# ESP8266_schematic.net
KiCad netlist of a schematic drawn in EAGLE
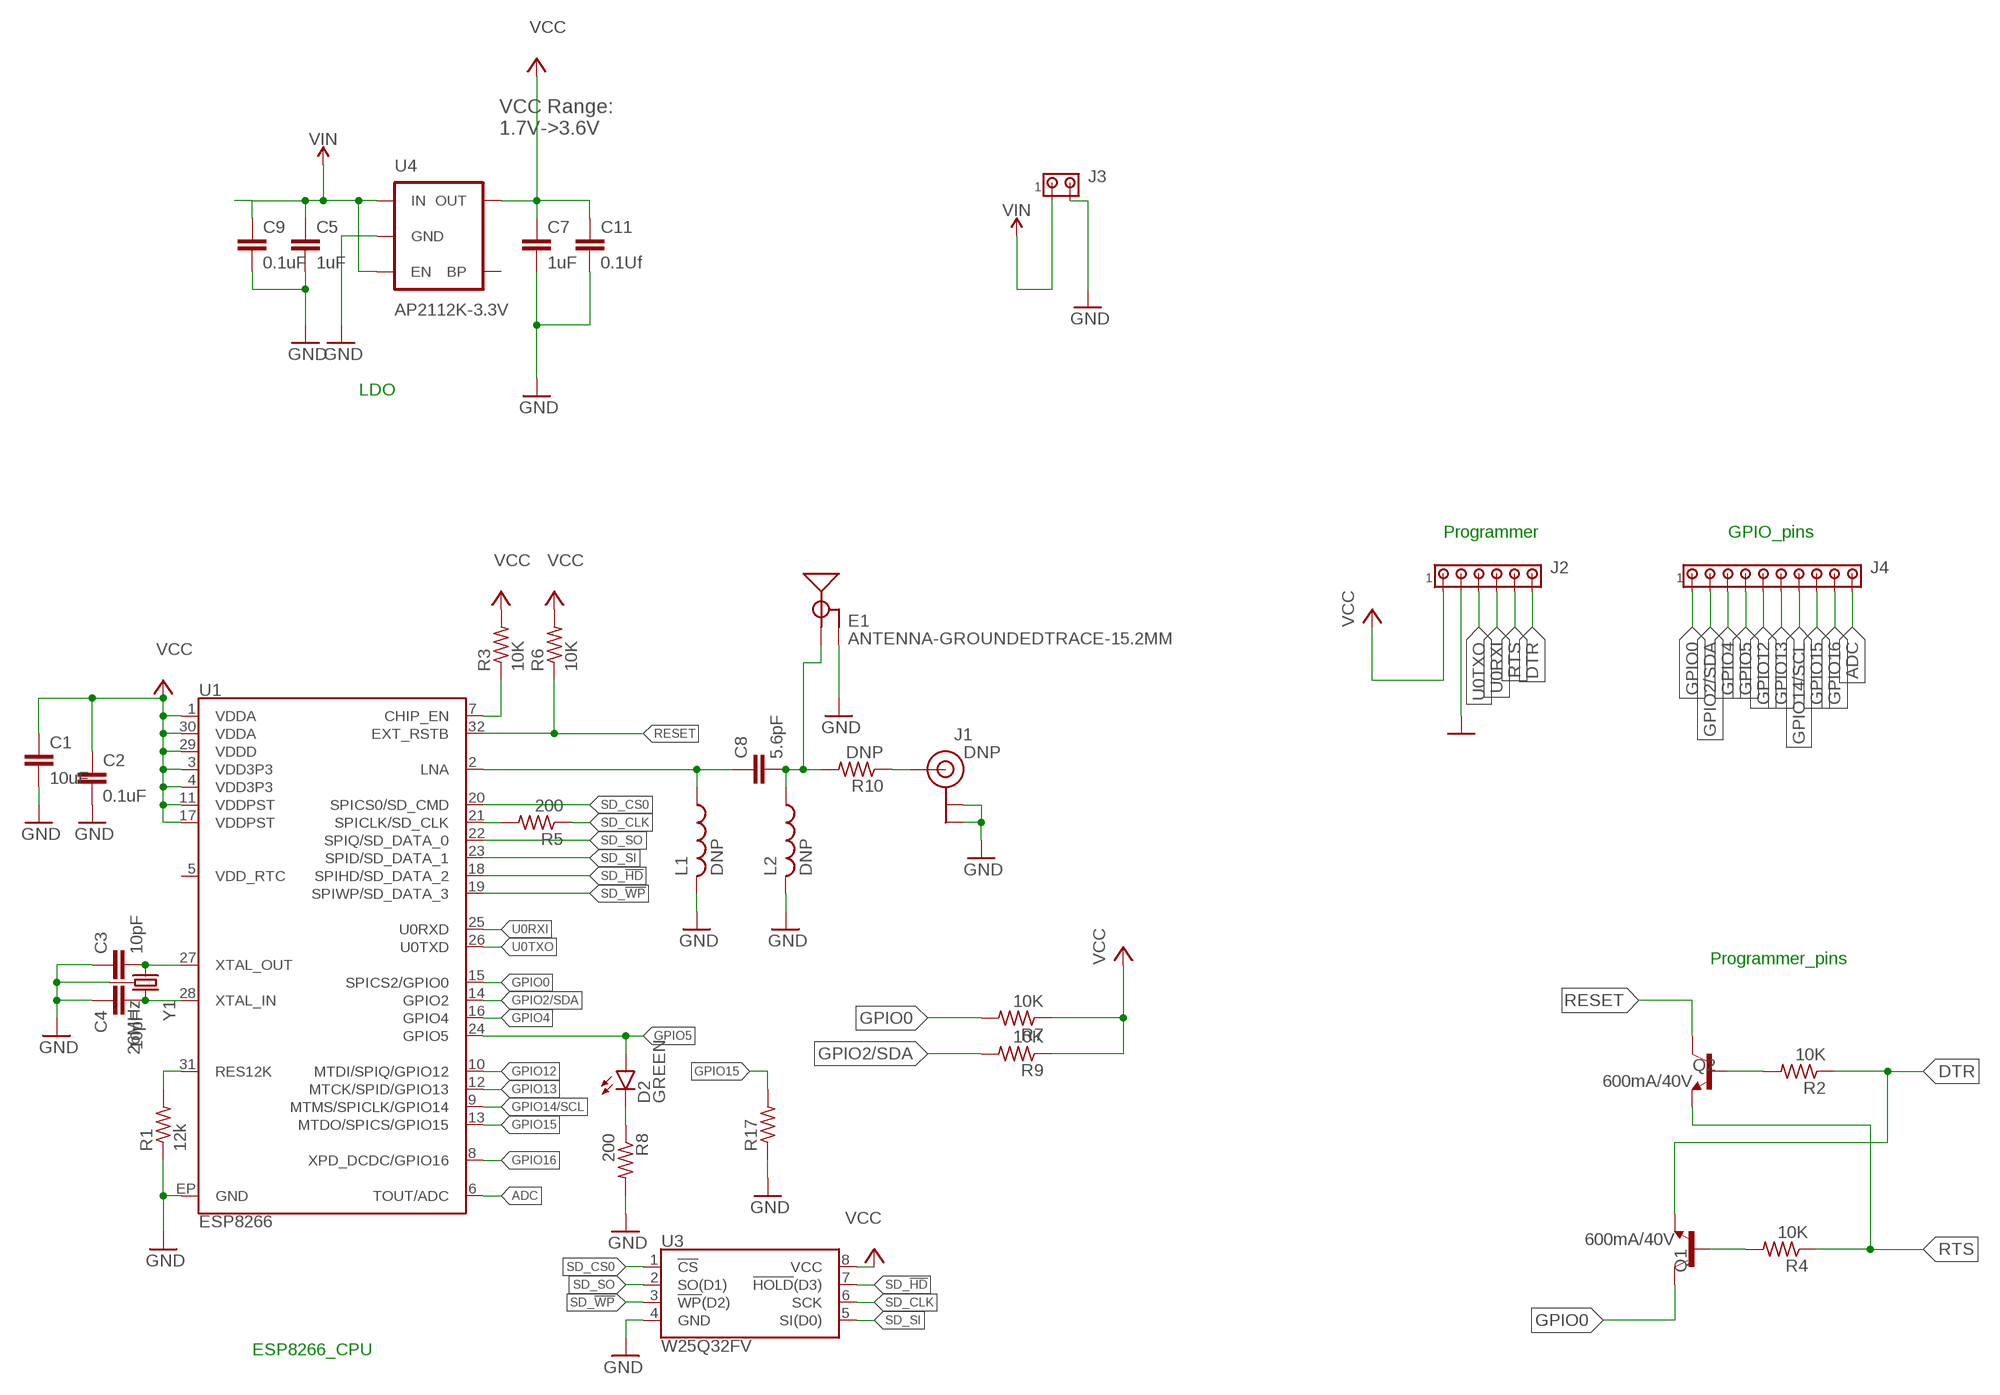
[diagram p0: schematic, sheet 1]

(export (version "E")
  (design (tool "Eeschema 10.0.6"))
  (components
    (comp (ref "C1")
      (value "10uF")
      (footprint "eagle-import:C0603")
      (libsource (lib "eagle-import") (part "resistor_C-EUC0603"))
    )
    (comp (ref "C2")
      (value "0.1uF")
      (footprint "eagle-import:C0603")
      (libsource (lib "eagle-import") (part "resistor_C-EUC0603"))
    )
    (comp (ref "C3")
      (value "10pF")
      (footprint "eagle-import:C0603")
      (libsource (lib "eagle-import") (part "C-EUC0603"))
    )
    (comp (ref "C4")
      (value "10pF")
      (footprint "eagle-import:C0603")
      (libsource (lib "eagle-import") (part "C-EUC0603"))
    )
    (comp (ref "C5")
      (value "1uF")
      (footprint "eagle-import:C0603")
      (libsource (lib "eagle-import") (part "C-EUC0603"))
    )
    (comp (ref "C7")
      (value "1uF")
      (footprint "eagle-import:C0603")
      (libsource (lib "eagle-import") (part "C-EUC0603"))
    )
    (comp (ref "C8")
      (value "5.6pF")
      (footprint "eagle-import:C0603")
      (libsource (lib "eagle-import") (part "C-EUC0603"))
    )
    (comp (ref "C9")
      (value "0.1uF")
      (footprint "eagle-import:C0603")
      (libsource (lib "eagle-import") (part "C-EUC0603"))
    )
    (comp (ref "C11")
      (value "0.1Uf")
      (footprint "eagle-import:C0603")
      (libsource (lib "eagle-import") (part "C-EUC0603"))
    )
    (comp (ref "D2")
      (value "GREEN")
      (footprint "eagle-import:LED-0603")
      (libsource (lib "eagle-import") (part "LED-GREEN0603"))
    )
    (comp (ref "E1")
      (value "ANTENNA-GROUNDEDTRACE-15.2MM")
      (footprint "eagle-import:TRACE_ANTENNA_2.4GHZ_15.2MM")
      (libsource (lib "eagle-import") (part "ANTENNA-GROUNDEDTRACE-15.2MM"))
    )
    (comp (ref "J1")
      (value "DNP")
      (footprint "eagle-import:U.FL")
      (libsource (lib "eagle-import") (part "U.FL"))
    )
    (comp (ref "J2")
      (value "MTA06-100")
      (footprint "eagle-import:10X06MTA")
      (libsource (lib "eagle-import") (part "MTA06-100"))
    )
    (comp (ref "J3")
      (value "MTA02-100")
      (footprint "eagle-import:10X02MTA")
      (libsource (lib "eagle-import") (part "MTA02-100"))
    )
    (comp (ref "J4")
      (value "MTA10-100")
      (footprint "eagle-import:10X10MTA")
      (libsource (lib "eagle-import") (part "MTA10-100"))
    )
    (comp (ref "L1")
      (value "DNP")
      (footprint "eagle-import:L0603")
      (libsource (lib "eagle-import") (part "L-USL0603"))
    )
    (comp (ref "L2")
      (value "DNP")
      (footprint "eagle-import:L0603")
      (libsource (lib "eagle-import") (part "L-USL0603"))
    )
    (comp (ref "Q1")
      (value "600mA/40V")
      (footprint "eagle-import:SOT23-3")
      (libsource (lib "eagle-import") (part "TRANS_NPN-MMBT2222AL"))
    )
    (comp (ref "Q2")
      (value "600mA/40V")
      (footprint "eagle-import:SOT23-3")
      (libsource (lib "eagle-import") (part "TRANS_NPN-MMBT2222AL"))
    )
    (comp (ref "R1")
      (value "12k")
      (footprint "eagle-import:R0805")
      (libsource (lib "eagle-import") (part "R-US_R0805"))
    )
    (comp (ref "R2")
      (value "10K")
      (footprint "eagle-import:R0805")
      (libsource (lib "eagle-import") (part "R-US_R0805"))
    )
    (comp (ref "R3")
      (value "10K")
      (footprint "eagle-import:R0805")
      (libsource (lib "eagle-import") (part "R-US_R0805"))
    )
    (comp (ref "R4")
      (value "10K")
      (footprint "eagle-import:R0805")
      (libsource (lib "eagle-import") (part "R-US_R0805"))
    )
    (comp (ref "R5")
      (value "200")
      (footprint "eagle-import:R0805")
      (libsource (lib "eagle-import") (part "R-US_R0805"))
    )
    (comp (ref "R6")
      (value "10K")
      (footprint "eagle-import:R0805")
      (libsource (lib "eagle-import") (part "R-US_R0805"))
    )
    (comp (ref "R7")
      (value "10K")
      (footprint "eagle-import:R0805")
      (libsource (lib "eagle-import") (part "R-US_R0805"))
    )
    (comp (ref "R8")
      (value "200")
      (footprint "eagle-import:R0805")
      (libsource (lib "eagle-import") (part "R-US_R0805"))
    )
    (comp (ref "R9")
      (value "10K")
      (footprint "eagle-import:R0805")
      (libsource (lib "eagle-import") (part "R-US_R0805"))
    )
    (comp (ref "R10")
      (value "DNP")
      (footprint "eagle-import:R0805")
      (libsource (lib "eagle-import") (part "R-US_R0805"))
    )
    (comp (ref "R17")
      (value "10K")
      (footprint "eagle-import:R0805")
      (libsource (lib "eagle-import") (part "R-US_R0805"))
    )
    (comp (ref "U1")
      (value "ESP8266")
      (footprint "eagle-import:QFN32")
      (libsource (lib "eagle-import") (part "ESP8266"))
    )
    (comp (ref "U3")
      (value "W25Q32FV")
      (footprint "eagle-import:SOIC-8")
      (libsource (lib "eagle-import") (part "W25Q32FVSS"))
    )
    (comp (ref "U4")
      (value "AP2112K-3.3V")
      (footprint "eagle-import:SOT23-5")
      (libsource (lib "eagle-import") (part "V_REG_LDOSMD"))
    )
    (comp (ref "Y1")
      (value "26MHz")
      (footprint "eagle-import:CRYSTAL-SMD-3.2X2.5")
      (libsource (lib "eagle-import") (part "CRYSTAL-GROUNDED3.2X2.5"))
    )
  )
  (nets
    (net (code "1") (name "/SD_~{HD}") (class "Default")
      (node (ref "U1") (pin "18") (pinfunction "SPIHD/SD_DATA_2_18") (pintype "bidirectional"))
      (node (ref "U3") (pin "7") (pinfunction "~{HOLD}(D3)_7") (pintype "bidirectional"))
    )
    (net (code "2") (name "/SD_~{WP}") (class "Default")
      (node (ref "U1") (pin "19") (pinfunction "SPIWP/SD_DATA_3_19") (pintype "bidirectional"))
      (node (ref "U3") (pin "3") (pinfunction "~{WP}(D2)_3") (pintype "bidirectional"))
    )
    (net (code "3") (name "ADC") (class "Default")
      (node (ref "J4") (pin "10") (pinfunction "10_10") (pintype "passive"))
      (node (ref "U1") (pin "6") (pinfunction "TOUT/ADC_6") (pintype "bidirectional"))
    )
    (net (code "4") (name "DTR") (class "Default")
      (node (ref "J2") (pin "6") (pinfunction "6_6") (pintype "passive"))
      (node (ref "Q1") (pin "2") (pinfunction "E_2") (pintype "passive"))
      (node (ref "R2") (pin "1") (pinfunction "1_1") (pintype "passive"))
    )
    (net (code "5") (name "GND") (class "Default")
      (node (ref "C1") (pin "2") (pinfunction "2_2") (pintype "passive"))
      (node (ref "C11") (pin "2") (pinfunction "2_2") (pintype "passive"))
      (node (ref "C2") (pin "2") (pinfunction "2_2") (pintype "passive"))
      (node (ref "C3") (pin "1") (pinfunction "1_1") (pintype "passive"))
      (node (ref "C4") (pin "1") (pinfunction "1_1") (pintype "passive"))
      (node (ref "C5") (pin "2") (pinfunction "2_2") (pintype "passive"))
      (node (ref "C7") (pin "2") (pinfunction "2_2") (pintype "passive"))
      (node (ref "C9") (pin "2") (pinfunction "2_2") (pintype "passive"))
      (node (ref "E1") (pin "GND") (pinfunction "GND_GND") (pintype "bidirectional"))
      (node (ref "J1") (pin "P$1") (pinfunction "GND_P$1") (pintype "bidirectional"))
      (node (ref "J1") (pin "P$2") (pinfunction "GND_P$2") (pintype "bidirectional"))
      (node (ref "J2") (pin "2") (pinfunction "2_2") (pintype "passive"))
      (node (ref "J3") (pin "2") (pinfunction "2_2") (pintype "passive"))
      (node (ref "L1") (pin "2") (pinfunction "2_2") (pintype "passive"))
      (node (ref "L2") (pin "2") (pinfunction "2_2") (pintype "passive"))
      (node (ref "R1") (pin "1") (pinfunction "1_1") (pintype "passive"))
      (node (ref "R17") (pin "1") (pinfunction "1_1") (pintype "passive"))
      (node (ref "R8") (pin "2") (pinfunction "2_2") (pintype "passive"))
      (node (ref "U1") (pin "EP") (pinfunction "GND_EP") (pintype "bidirectional"))
      (node (ref "U3") (pin "4") (pinfunction "GND_4") (pintype "bidirectional"))
      (node (ref "U4") (pin "2") (pinfunction "GND_2") (pintype "input"))
      (node (ref "Y1") (pin "2") (pinfunction "GND_2") (pintype "passive"))
      (node (ref "Y1") (pin "4") (pinfunction "GND_4") (pintype "passive"))
    )
    (net (code "6") (name "GPIO0") (class "Default")
      (node (ref "J4") (pin "1") (pinfunction "1_1") (pintype "passive"))
      (node (ref "Q1") (pin "3") (pinfunction "C_3") (pintype "passive"))
      (node (ref "R7") (pin "2") (pinfunction "2_2") (pintype "passive"))
      (node (ref "U1") (pin "15") (pinfunction "SPICS2/GPIO0_15") (pintype "bidirectional"))
    )
    (net (code "7") (name "GPIO2{slash}SDA") (class "Default")
      (node (ref "J4") (pin "2") (pinfunction "2_2") (pintype "passive"))
      (node (ref "R9") (pin "2") (pinfunction "2_2") (pintype "passive"))
      (node (ref "U1") (pin "14") (pinfunction "GPIO2_14") (pintype "bidirectional"))
    )
    (net (code "8") (name "GPIO4") (class "Default")
      (node (ref "J4") (pin "3") (pinfunction "3_3") (pintype "passive"))
      (node (ref "U1") (pin "16") (pinfunction "GPIO4_16") (pintype "bidirectional"))
    )
    (net (code "9") (name "GPIO5") (class "Default")
      (node (ref "D2") (pin "A") (pinfunction "A_A") (pintype "passive"))
      (node (ref "J4") (pin "4") (pinfunction "4_4") (pintype "passive"))
      (node (ref "U1") (pin "24") (pinfunction "GPIO5_24") (pintype "bidirectional"))
    )
    (net (code "10") (name "GPIO12") (class "Default")
      (node (ref "J4") (pin "5") (pinfunction "5_5") (pintype "passive"))
      (node (ref "U1") (pin "10") (pinfunction "MTDI/SPIQ/GPIO12_10") (pintype "bidirectional"))
    )
    (net (code "11") (name "GPIO13") (class "Default")
      (node (ref "J4") (pin "6") (pinfunction "6_6") (pintype "passive"))
      (node (ref "U1") (pin "12") (pinfunction "MTCK/SPID/GPIO13_12") (pintype "bidirectional"))
    )
    (net (code "12") (name "GPIO14{slash}SCL") (class "Default")
      (node (ref "J4") (pin "7") (pinfunction "7_7") (pintype "passive"))
      (node (ref "U1") (pin "9") (pinfunction "MTMS/SPICLK/GPIO14_9") (pintype "bidirectional"))
    )
    (net (code "13") (name "GPIO15") (class "Default")
      (node (ref "J4") (pin "8") (pinfunction "8_8") (pintype "passive"))
      (node (ref "R17") (pin "2") (pinfunction "2_2") (pintype "passive"))
      (node (ref "U1") (pin "13") (pinfunction "MTDO/SPICS/GPIO15_13") (pintype "bidirectional"))
    )
    (net (code "14") (name "GPIO16") (class "Default")
      (node (ref "J4") (pin "9") (pinfunction "9_9") (pintype "passive"))
      (node (ref "U1") (pin "8") (pinfunction "XPD_DCDC/GPIO16_8") (pintype "bidirectional"))
    )
    (net (code "15") (name "Net-(D2-PadC)") (class "Default")
      (node (ref "D2") (pin "C") (pinfunction "C_C") (pintype "passive"))
      (node (ref "R8") (pin "1") (pinfunction "1_1") (pintype "passive"))
    )
    (net (code "16") (name "Net-(E1-SIGNAL)") (class "Default")
      (node (ref "C8") (pin "2") (pinfunction "2_2") (pintype "passive"))
      (node (ref "E1") (pin "ANT") (pinfunction "SIGNAL_ANT") (pintype "bidirectional"))
      (node (ref "L2") (pin "1") (pinfunction "1_1") (pintype "passive"))
      (node (ref "R10") (pin "2") (pinfunction "2_2") (pintype "passive"))
    )
    (net (code "17") (name "Net-(J1-SIGNAL)") (class "Default")
      (node (ref "J1") (pin "P$3") (pinfunction "SIGNAL_P$3") (pintype "bidirectional"))
      (node (ref "R10") (pin "1") (pinfunction "1_1") (pintype "passive"))
    )
    (net (code "18") (name "Net-(Q1-B)") (class "Default")
      (node (ref "Q1") (pin "1") (pinfunction "B_1") (pintype "passive"))
      (node (ref "R4") (pin "2") (pinfunction "2_2") (pintype "passive"))
    )
    (net (code "19") (name "Net-(Q2-B)") (class "Default")
      (node (ref "Q2") (pin "1") (pinfunction "B_1") (pintype "passive"))
      (node (ref "R2") (pin "2") (pinfunction "2_2") (pintype "passive"))
    )
    (net (code "20") (name "Net-(U1-CHIP_EN)") (class "Default")
      (node (ref "R3") (pin "1") (pinfunction "1_1") (pintype "passive"))
      (node (ref "U1") (pin "7") (pinfunction "CHIP_EN_7") (pintype "bidirectional"))
    )
    (net (code "21") (name "Net-(U1-LNA)") (class "Default")
      (node (ref "C8") (pin "1") (pinfunction "1_1") (pintype "passive"))
      (node (ref "L1") (pin "1") (pinfunction "1_1") (pintype "passive"))
      (node (ref "U1") (pin "2") (pinfunction "LNA_2") (pintype "bidirectional"))
    )
    (net (code "22") (name "Net-(U1-RES12K)") (class "Default")
      (node (ref "R1") (pin "2") (pinfunction "2_2") (pintype "passive"))
      (node (ref "U1") (pin "31") (pinfunction "RES12K_31") (pintype "bidirectional"))
    )
    (net (code "23") (name "Net-(U1-SPICLK{slash}SD_CLK)") (class "Default")
      (node (ref "R5") (pin "2") (pinfunction "2_2") (pintype "passive"))
      (node (ref "U1") (pin "21") (pinfunction "SPICLK/SD_CLK_21") (pintype "bidirectional"))
    )
    (net (code "24") (name "Net-(U1-XTAL_IN)") (class "Default")
      (node (ref "C4") (pin "2") (pinfunction "2_2") (pintype "passive"))
      (node (ref "U1") (pin "28") (pinfunction "XTAL_IN_28") (pintype "bidirectional"))
      (node (ref "Y1") (pin "3") (pinfunction "2_3") (pintype "passive"))
    )
    (net (code "25") (name "Net-(U1-XTAL_OUT)") (class "Default")
      (node (ref "C3") (pin "2") (pinfunction "2_2") (pintype "passive"))
      (node (ref "U1") (pin "27") (pinfunction "XTAL_OUT_27") (pintype "bidirectional"))
      (node (ref "Y1") (pin "1") (pinfunction "1_1") (pintype "passive"))
    )
    (net (code "26") (name "RESET") (class "Default")
      (node (ref "Q2") (pin "3") (pinfunction "C_3") (pintype "passive"))
      (node (ref "R6") (pin "1") (pinfunction "1_1") (pintype "passive"))
      (node (ref "U1") (pin "32") (pinfunction "EXT_RSTB_32") (pintype "bidirectional"))
    )
    (net (code "27") (name "RTS") (class "Default")
      (node (ref "J2") (pin "5") (pinfunction "5_5") (pintype "passive"))
      (node (ref "Q2") (pin "2") (pinfunction "E_2") (pintype "passive"))
      (node (ref "R4") (pin "1") (pinfunction "1_1") (pintype "passive"))
    )
    (net (code "28") (name "SD_CLK") (class "Default")
      (node (ref "R5") (pin "1") (pinfunction "1_1") (pintype "passive"))
      (node (ref "U3") (pin "6") (pinfunction "SCK_6") (pintype "bidirectional"))
    )
    (net (code "29") (name "SD_CS0") (class "Default")
      (node (ref "U1") (pin "20") (pinfunction "SPICS0/SD_CMD_20") (pintype "bidirectional"))
      (node (ref "U3") (pin "1") (pinfunction "~{CS}_1") (pintype "bidirectional"))
    )
    (net (code "30") (name "SD_SI") (class "Default")
      (node (ref "U1") (pin "23") (pinfunction "SPID/SD_DATA_1_23") (pintype "bidirectional"))
      (node (ref "U3") (pin "5") (pinfunction "SI(D0)_5") (pintype "bidirectional"))
    )
    (net (code "31") (name "SD_SO") (class "Default")
      (node (ref "U1") (pin "22") (pinfunction "SPIQ/SD_DATA_0_22") (pintype "bidirectional"))
      (node (ref "U3") (pin "2") (pinfunction "SO(D1)_2") (pintype "bidirectional"))
    )
    (net (code "32") (name "U0RXI") (class "Default")
      (node (ref "J2") (pin "4") (pinfunction "4_4") (pintype "passive"))
      (node (ref "U1") (pin "25") (pinfunction "U0RXD_25") (pintype "bidirectional"))
    )
    (net (code "33") (name "U0TXO") (class "Default")
      (node (ref "J2") (pin "3") (pinfunction "3_3") (pintype "passive"))
      (node (ref "U1") (pin "26") (pinfunction "U0TXD_26") (pintype "bidirectional"))
    )
    (net (code "34") (name "VCC") (class "Default")
      (node (ref "C1") (pin "1") (pinfunction "1_1") (pintype "passive"))
      (node (ref "C11") (pin "1") (pinfunction "1_1") (pintype "passive"))
      (node (ref "C2") (pin "1") (pinfunction "1_1") (pintype "passive"))
      (node (ref "C7") (pin "1") (pinfunction "1_1") (pintype "passive"))
      (node (ref "J2") (pin "1") (pinfunction "1_1") (pintype "passive"))
      (node (ref "R3") (pin "2") (pinfunction "2_2") (pintype "passive"))
      (node (ref "R6") (pin "2") (pinfunction "2_2") (pintype "passive"))
      (node (ref "R7") (pin "1") (pinfunction "1_1") (pintype "passive"))
      (node (ref "R9") (pin "1") (pinfunction "1_1") (pintype "passive"))
      (node (ref "U1") (pin "1") (pinfunction "VDDA_1") (pintype "bidirectional"))
      (node (ref "U1") (pin "11") (pinfunction "VDDPST_11") (pintype "bidirectional"))
      (node (ref "U1") (pin "17") (pinfunction "VDDPST_17") (pintype "bidirectional"))
      (node (ref "U1") (pin "29") (pinfunction "VDDD_29") (pintype "bidirectional"))
      (node (ref "U1") (pin "3") (pinfunction "VDD3P3_3") (pintype "bidirectional"))
      (node (ref "U1") (pin "30") (pinfunction "VDDA_30") (pintype "bidirectional"))
      (node (ref "U1") (pin "4") (pinfunction "VDD3P3_4") (pintype "bidirectional"))
      (node (ref "U3") (pin "8") (pinfunction "VCC_8") (pintype "bidirectional"))
      (node (ref "U4") (pin "5") (pinfunction "OUT_5") (pintype "passive"))
    )
    (net (code "35") (name "VIN") (class "Default")
      (node (ref "C5") (pin "1") (pinfunction "1_1") (pintype "passive"))
      (node (ref "C9") (pin "1") (pinfunction "1_1") (pintype "passive"))
      (node (ref "J3") (pin "1") (pinfunction "1_1") (pintype "passive"))
      (node (ref "U4") (pin "1") (pinfunction "IN_1") (pintype "input"))
      (node (ref "U4") (pin "3") (pinfunction "EN_3") (pintype "input"))
    )
    (net (code "36") (name "unconnected-(U1-VDD_RTC-Pad5)") (class "Default")
      (node (ref "U1") (pin "5") (pinfunction "VDD_RTC_5") (pintype "bidirectional"))
    )
    (net (code "37") (name "unconnected-(U4-BP-Pad4)") (class "Default")
      (node (ref "U4") (pin "4") (pinfunction "BP_4") (pintype "input"))
    )
  )
)
